# cnc.net
KiCad netlist of a schematic drawn in Altium Designer
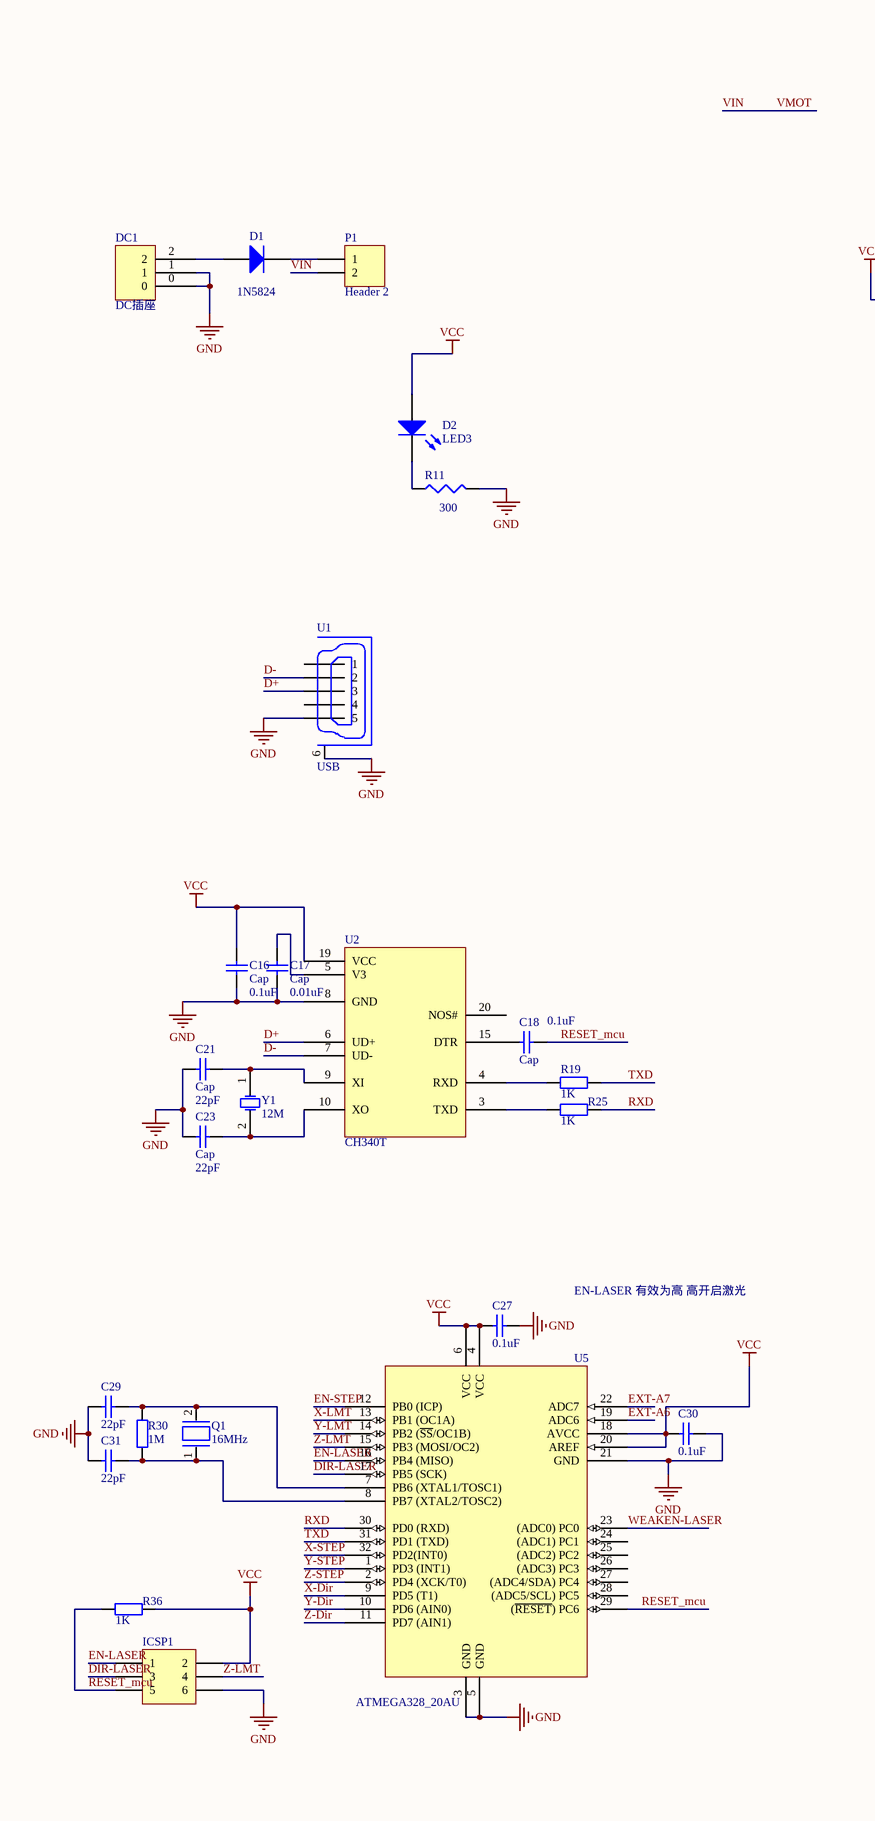
[diagram p0: cnc.SchDoc, left]
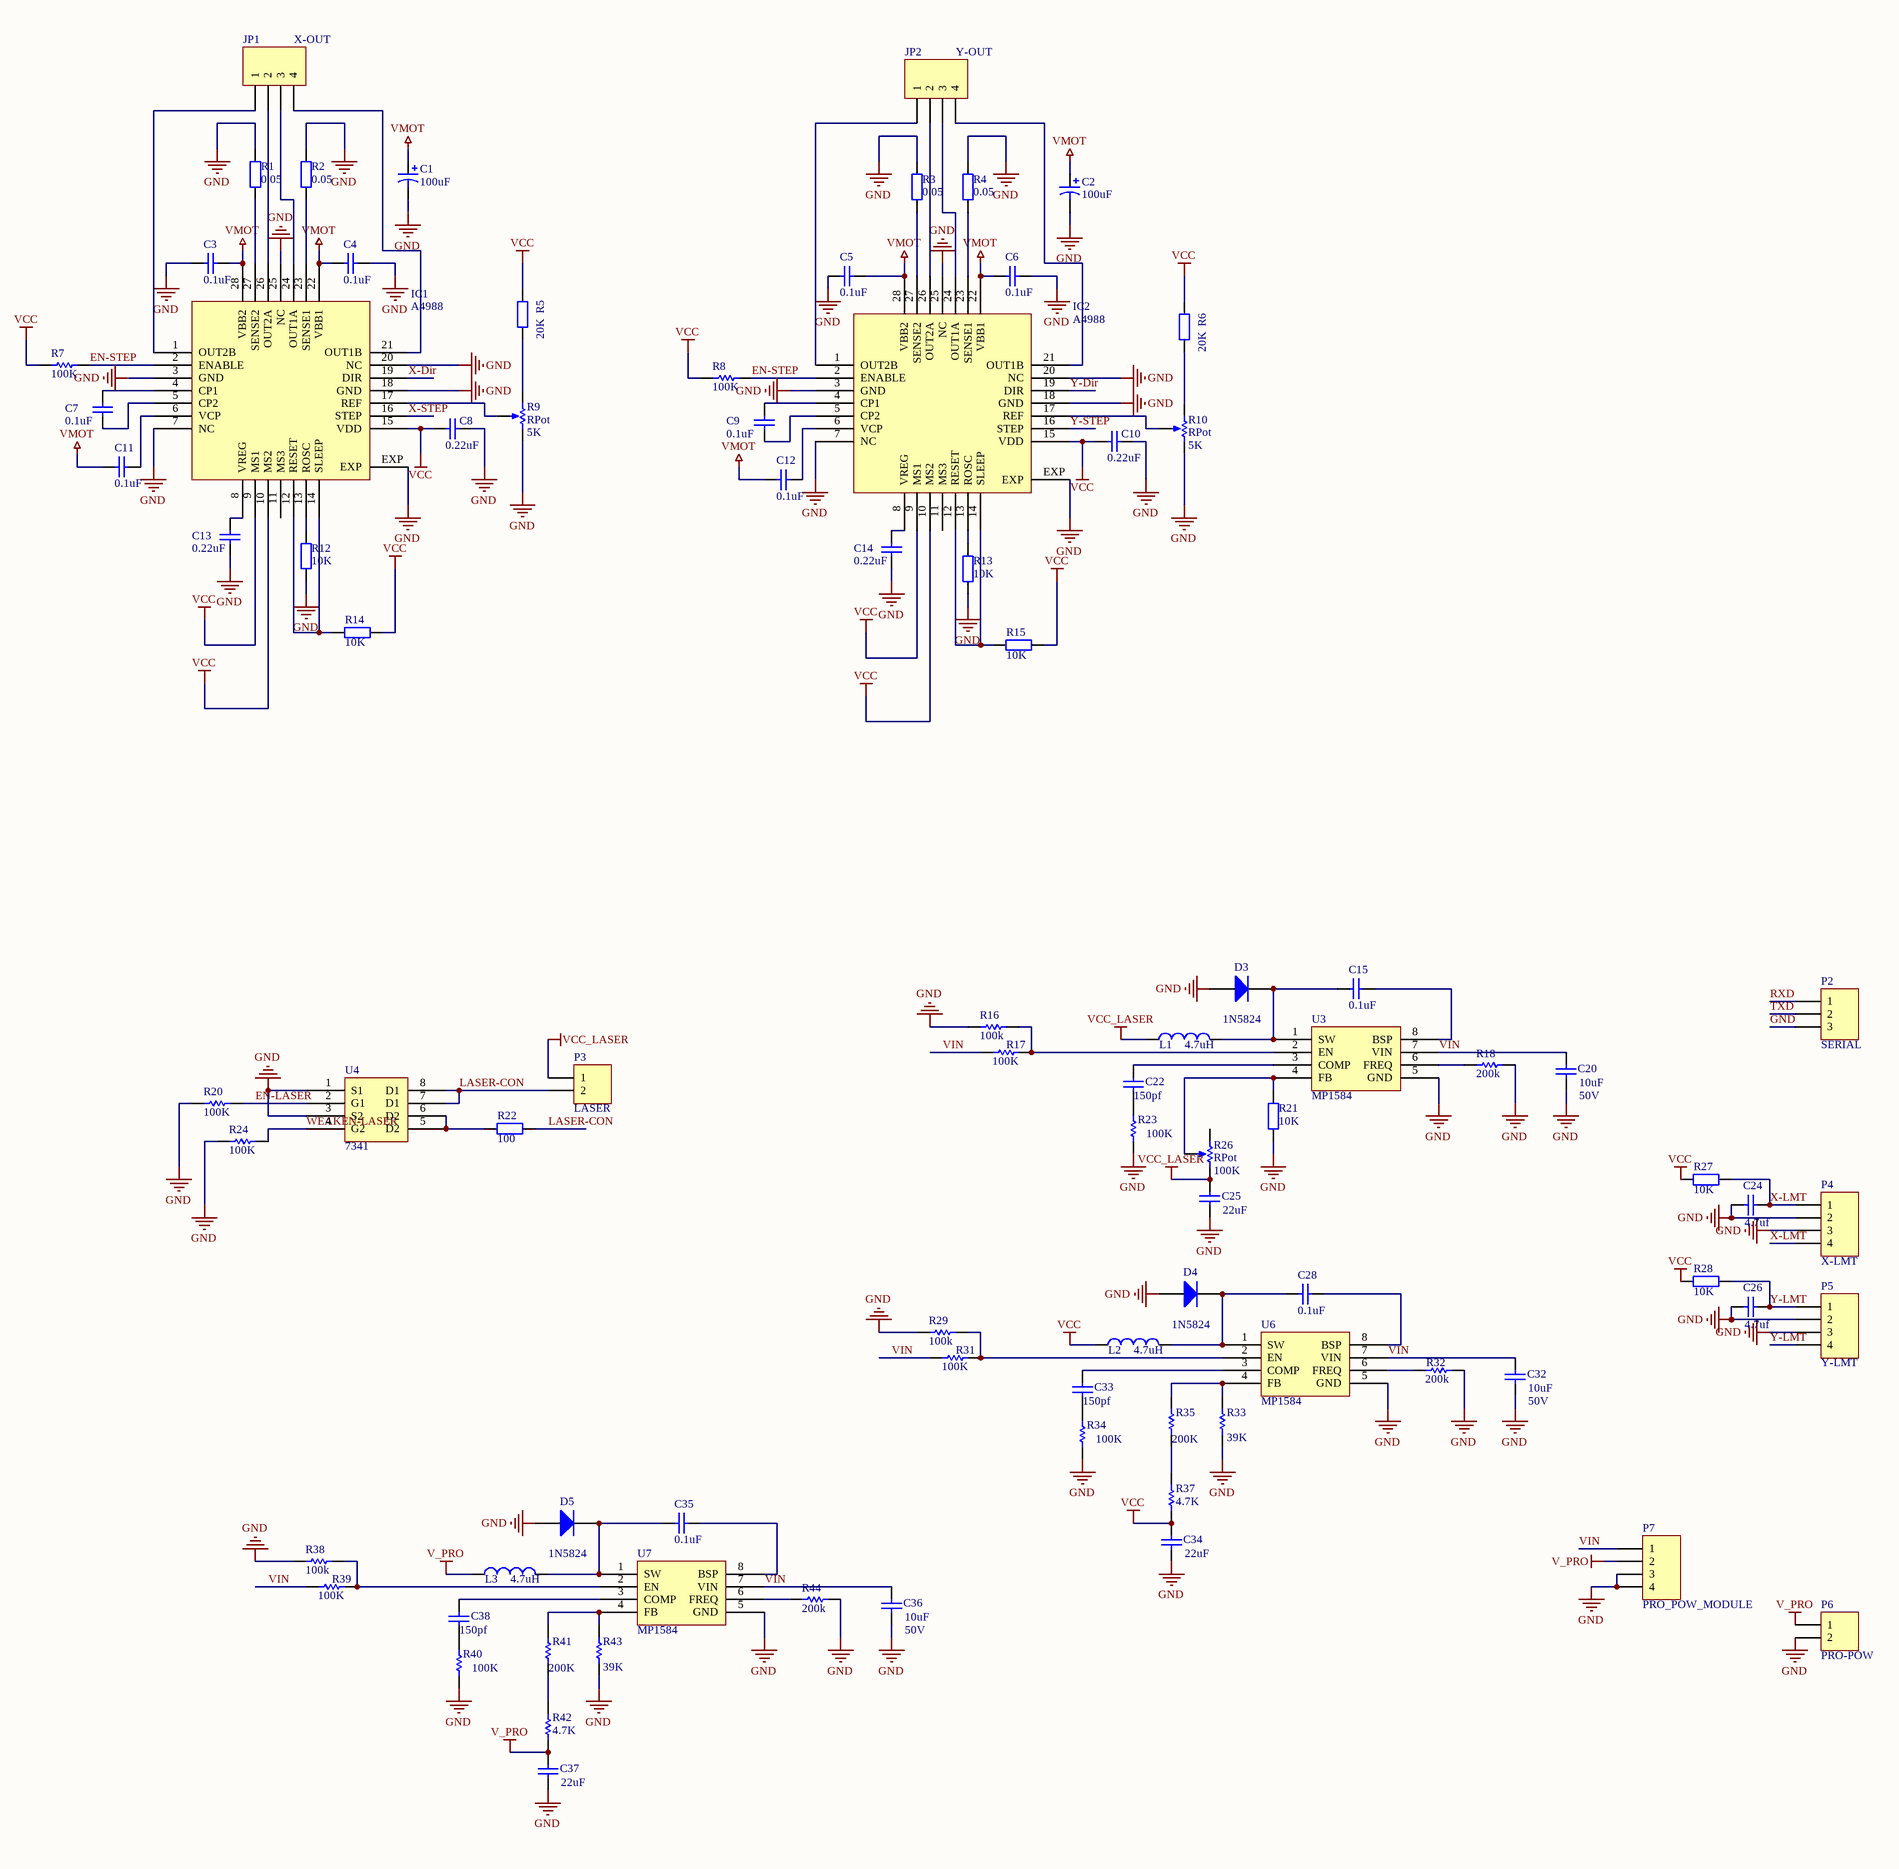
[diagram p1: cnc.SchDoc, right]

(export (version "E")
  (design (tool "Eeschema 10.0.6"))
  (components
    (comp (ref "C1")
      (value "100uF")
      (footprint "CD6032")
      (description "Polarized Capacitor (Radial)")
      (fields (field (name "Comment") "Cap Pol1") (field (name "PUBLISHER") "Altium Limited"))
      (libsource (lib "Miscellaneous Devices") (part "Cap Pol1"))
    )
    (comp (ref "C2")
      (value "100uF")
      (footprint "CD6032")
      (description "Polarized Capacitor (Radial)")
      (fields (field (name "Comment") "Cap Pol1") (field (name "PUBLISHER") "Altium Limited"))
      (libsource (lib "Miscellaneous Devices") (part "Cap Pol1"))
    )
    (comp (ref "C3")
      (value "0.1uF")
      (footprint "C0603")
      (description "Capacitor")
      (fields (field (name "Comment") "Cap") (field (name "PUBLISHER") "Altium Limited"))
      (libsource (lib "Miscellaneous Devices") (part "Cap"))
    )
    (comp (ref "C4")
      (value "0.1uF")
      (footprint "C0603")
      (description "Capacitor")
      (fields (field (name "Comment") "Cap") (field (name "PUBLISHER") "Altium Limited"))
      (libsource (lib "Miscellaneous Devices") (part "Cap"))
    )
    (comp (ref "C5")
      (value "0.1uF")
      (footprint "C0603")
      (description "Capacitor")
      (fields (field (name "Comment") "Cap") (field (name "PUBLISHER") "Altium Limited"))
      (libsource (lib "Miscellaneous Devices") (part "Cap"))
    )
    (comp (ref "C6")
      (value "0.1uF")
      (footprint "C0603")
      (description "Capacitor")
      (fields (field (name "Comment") "Cap") (field (name "PUBLISHER") "Altium Limited"))
      (libsource (lib "Miscellaneous Devices") (part "Cap"))
    )
    (comp (ref "C7")
      (value "0.1uF")
      (footprint "C0603")
      (description "Capacitor")
      (fields (field (name "Comment") "Cap") (field (name "PUBLISHER") "Altium Limited"))
      (libsource (lib "Miscellaneous Devices") (part "Cap"))
    )
    (comp (ref "C8")
      (value "0.22uF")
      (footprint "C0603")
      (description "Capacitor")
      (fields (field (name "Comment") "Cap") (field (name "PUBLISHER") "Altium Limited"))
      (libsource (lib "Miscellaneous Devices") (part "Cap"))
    )
    (comp (ref "C9")
      (value "0.1uF")
      (footprint "C0603")
      (description "Capacitor")
      (fields (field (name "Comment") "Cap") (field (name "PUBLISHER") "Altium Limited"))
      (libsource (lib "Miscellaneous Devices") (part "Cap"))
    )
    (comp (ref "C10")
      (value "0.22uF")
      (footprint "C0603")
      (description "Capacitor")
      (fields (field (name "Comment") "Cap") (field (name "PUBLISHER") "Altium Limited"))
      (libsource (lib "Miscellaneous Devices") (part "Cap"))
    )
    (comp (ref "C11")
      (value "0.1uF")
      (footprint "C0603")
      (description "Capacitor")
      (fields (field (name "Comment") "Cap") (field (name "PUBLISHER") "Altium Limited"))
      (libsource (lib "Miscellaneous Devices") (part "Cap"))
    )
    (comp (ref "C12")
      (value "0.1uF")
      (footprint "C0603")
      (description "Capacitor")
      (fields (field (name "Comment") "Cap") (field (name "PUBLISHER") "Altium Limited"))
      (libsource (lib "Miscellaneous Devices") (part "Cap"))
    )
    (comp (ref "C13")
      (value "0.22uF")
      (footprint "C0603")
      (description "Capacitor")
      (fields (field (name "Comment") "Cap") (field (name "PUBLISHER") "Altium Limited"))
      (libsource (lib "Miscellaneous Devices") (part "Cap"))
    )
    (comp (ref "C14")
      (value "0.22uF")
      (footprint "C0603")
      (description "Capacitor")
      (fields (field (name "Comment") "Cap") (field (name "PUBLISHER") "Altium Limited"))
      (libsource (lib "Miscellaneous Devices") (part "Cap"))
    )
    (comp (ref "C15")
      (value "0.1uF")
      (footprint "C0603")
      (description "Capacitor")
      (fields (field (name "Comment") "Cap") (field (name "PUBLISHER") "Altium Limited"))
      (libsource (lib "Miscellaneous Devices") (part "Cap"))
    )
    (comp (ref "C16")
      (value "Cap")
      (footprint "C0603")
      (description "Capacitor")
      (fields (field (name "ALTIUM_VALUE") "0.1uF") (field (name "PUBLISHER") "Altium Limited"))
      (libsource (lib "Miscellaneous Devices") (part "Cap"))
    )
    (comp (ref "C17")
      (value "Cap")
      (footprint "C0603")
      (description "Capacitor")
      (fields (field (name "ALTIUM_VALUE") "0.01uF") (field (name "PUBLISHER") "Altium Limited"))
      (libsource (lib "Miscellaneous Devices") (part "Cap"))
    )
    (comp (ref "C18")
      (value "Cap")
      (footprint "C0603")
      (description "Capacitor")
      (fields (field (name "ALTIUM_VALUE") "0.1uF") (field (name "PUBLISHER") "Altium Limited"))
      (libsource (lib "Miscellaneous Devices") (part "Cap"))
    )
    (comp (ref "C20")
      (value "50V")
      (footprint "C0603")
      (description "Capacitor")
      (fields (field (name "ALTIUM_VALUE") "10uF") (field (name "PUBLISHER") "Altium Limited"))
      (libsource (lib "Miscellaneous Devices") (part "Cap"))
    )
    (comp (ref "C21")
      (value "Cap")
      (footprint "C0603")
      (description "Capacitor")
      (fields (field (name "ALTIUM_VALUE") "22pF") (field (name "PUBLISHER") "Altium Limited"))
      (libsource (lib "Miscellaneous Devices") (part "Cap"))
    )
    (comp (ref "C22")
      (value "150pf")
      (footprint "C0603")
      (description "Capacitor")
      (fields (field (name "Comment") "Cap") (field (name "PUBLISHER") "Altium Limited"))
      (libsource (lib "Miscellaneous Devices") (part "Cap"))
    )
    (comp (ref "C23")
      (value "Cap")
      (footprint "C0603")
      (description "Capacitor")
      (fields (field (name "ALTIUM_VALUE") "22pF") (field (name "PUBLISHER") "Altium Limited"))
      (libsource (lib "Miscellaneous Devices") (part "Cap"))
    )
    (comp (ref "C24")
      (value "4.7uf")
      (footprint "C0603")
      (description "Capacitor")
      (fields (field (name "Comment") "Cap") (field (name "PUBLISHER") "Altium Limited"))
      (libsource (lib "Miscellaneous Devices") (part "Cap"))
    )
    (comp (ref "C25")
      (value "22uF")
      (footprint "C0603")
      (description "Capacitor")
      (fields (field (name "Comment") "Cap") (field (name "PUBLISHER") "Altium Limited"))
      (libsource (lib "Miscellaneous Devices") (part "Cap"))
    )
    (comp (ref "C26")
      (value "4.7uf")
      (footprint "C0603")
      (description "Capacitor")
      (fields (field (name "Comment") "Cap") (field (name "PUBLISHER") "Altium Limited"))
      (libsource (lib "Miscellaneous Devices") (part "Cap"))
    )
    (comp (ref "C27")
      (value "0.1uF")
      (footprint "C0603")
      (description "Capacitor")
      (fields (field (name "Comment") "Cap") (field (name "PUBLISHER") "Altium Limited"))
      (libsource (lib "Miscellaneous Devices") (part "Cap"))
    )
    (comp (ref "C28")
      (value "0.1uF")
      (footprint "C0603")
      (description "Capacitor")
      (fields (field (name "Comment") "Cap") (field (name "PUBLISHER") "Altium Limited"))
      (libsource (lib "Miscellaneous Devices") (part "Cap"))
    )
    (comp (ref "C29")
      (value "22pF")
      (footprint "C0603")
      (description "Capacitor")
      (fields (field (name "Comment") "Cap") (field (name "PUBLISHER") "Altium Limited"))
      (libsource (lib "Miscellaneous Devices") (part "Cap"))
    )
    (comp (ref "C30")
      (value "0.1uF")
      (footprint "C0603")
      (description "Capacitor")
      (fields (field (name "Comment") "Cap") (field (name "PUBLISHER") "Altium Limited"))
      (libsource (lib "Miscellaneous Devices") (part "Cap"))
    )
    (comp (ref "C31")
      (value "22pF")
      (footprint "C0603")
      (description "Capacitor")
      (fields (field (name "Comment") "Cap") (field (name "PUBLISHER") "Altium Limited"))
      (libsource (lib "Miscellaneous Devices") (part "Cap"))
    )
    (comp (ref "C32")
      (value "50V")
      (footprint "C0603")
      (description "Capacitor")
      (fields (field (name "ALTIUM_VALUE") "10uF") (field (name "PUBLISHER") "Altium Limited"))
      (libsource (lib "Miscellaneous Devices") (part "Cap"))
    )
    (comp (ref "C33")
      (value "150pf")
      (footprint "C0603")
      (description "Capacitor")
      (fields (field (name "Comment") "Cap") (field (name "PUBLISHER") "Altium Limited"))
      (libsource (lib "Miscellaneous Devices") (part "Cap"))
    )
    (comp (ref "C34")
      (value "22uF")
      (footprint "C0603")
      (description "Capacitor")
      (fields (field (name "Comment") "Cap") (field (name "PUBLISHER") "Altium Limited"))
      (libsource (lib "Miscellaneous Devices") (part "Cap"))
    )
    (comp (ref "C35")
      (value "0.1uF")
      (footprint "C0603")
      (description "Capacitor")
      (fields (field (name "Comment") "Cap") (field (name "PUBLISHER") "Altium Limited"))
      (libsource (lib "Miscellaneous Devices") (part "Cap"))
    )
    (comp (ref "C36")
      (value "50V")
      (footprint "C0603")
      (description "Capacitor")
      (fields (field (name "ALTIUM_VALUE") "10uF") (field (name "PUBLISHER") "Altium Limited"))
      (libsource (lib "Miscellaneous Devices") (part "Cap"))
    )
    (comp (ref "C37")
      (value "22uF")
      (footprint "C0603")
      (description "Capacitor")
      (fields (field (name "Comment") "Cap") (field (name "PUBLISHER") "Altium Limited"))
      (libsource (lib "Miscellaneous Devices") (part "Cap"))
    )
    (comp (ref "C38")
      (value "150pf")
      (footprint "C0603")
      (description "Capacitor")
      (fields (field (name "Comment") "Cap") (field (name "PUBLISHER") "Altium Limited"))
      (libsource (lib "Miscellaneous Devices") (part "Cap"))
    )
    (comp (ref "D1")
      (value "1N5824")
      (footprint "SS34")
      (description "1 Amp General Purpose Rectifier")
      (fields (field (name "PUBLISHER") "Altium Limited"))
      (libsource (lib "Miscellaneous Devices") (part "Diode 1N4007"))
    )
    (comp (ref "D2")
      (value "LED3")
      (footprint "LED")
      (description "Typical BLUE SiC LED")
      (fields (field (name "PUBLISHER") "Altium Limited"))
      (libsource (lib "Miscellaneous Devices") (part "LED3"))
    )
    (comp (ref "D3")
      (value "1N5824")
      (footprint "SS34")
      (description "1 Amp General Purpose Rectifier")
      (fields (field (name "PUBLISHER") "Altium Limited"))
      (libsource (lib "Miscellaneous Devices") (part "Diode 1N4007"))
    )
    (comp (ref "D4")
      (value "1N5824")
      (footprint "SS34")
      (description "1 Amp General Purpose Rectifier")
      (fields (field (name "PUBLISHER") "Altium Limited"))
      (libsource (lib "Miscellaneous Devices") (part "Diode 1N4007"))
    )
    (comp (ref "D5")
      (value "1N5824")
      (footprint "SS34")
      (description "1 Amp General Purpose Rectifier")
      (fields (field (name "PUBLISHER") "Altium Limited"))
      (libsource (lib "Miscellaneous Devices") (part "Diode 1N4007"))
    )
    (comp (ref "DC1") (value "DC插座") (footprint "DC座") (libsource (lib "dc") (part "DC插座")))
    (comp (ref "IC1") (value "A4988") (footprint "QFN28ET") (libsource (lib "Schlib1") (part "A4988")))
    (comp (ref "IC2") (value "A4988") (footprint "QFN28ET") (libsource (lib "Schlib1") (part "A4988")))
    (comp (ref "ICSP1")
      (value "Header 3X2")
      (footprint "HDR2X3")
      (description "Header, 3-Pin, Dual row")
      (fields (field (name "PUBLISHER") "Altium Limited"))
      (libsource (lib "Miscellaneous Connectors") (part "Header 3X2"))
    )
    (comp (ref "JP1")
      (value "X-OUT")
      (footprint "XH-2.54-4")
      (description "Header, 4-Pin")
      (fields (field (name "PUBLISHER") "Altium Limited"))
      (libsource (lib "") (part "Header 4_1"))
    )
    (comp (ref "JP2")
      (value "Y-OUT")
      (footprint "XH-2.54-4")
      (description "Header, 4-Pin")
      (fields (field (name "PUBLISHER") "Altium Limited"))
      (libsource (lib "") (part "Header 4_1"))
    )
    (comp (ref "L1")
      (value "4.7uH")
      (footprint "L_1584")
      (description "Inductor")
      (fields (field (name "PUBLISHER") "Altium Limited"))
      (libsource (lib "Miscellaneous Devices") (part "Inductor"))
    )
    (comp (ref "L2")
      (value "4.7uH")
      (footprint "L_1584")
      (description "Inductor")
      (fields (field (name "PUBLISHER") "Altium Limited"))
      (libsource (lib "Miscellaneous Devices") (part "Inductor"))
    )
    (comp (ref "L3")
      (value "4.7uH")
      (footprint "L_1584")
      (description "Inductor")
      (fields (field (name "PUBLISHER") "Altium Limited"))
      (libsource (lib "Miscellaneous Devices") (part "Inductor"))
    )
    (comp (ref "P1")
      (value "Header 2")
      (footprint "XH-2.54-2")
      (description "Header, 2-Pin")
      (fields (field (name "PUBLISHER") "Altium Limited"))
      (libsource (lib "Miscellaneous Connectors") (part "Header 2"))
    )
    (comp (ref "P2")
      (value "SERIAL")
      (footprint "HDR1X3")
      (description "Header, 3-Pin")
      (fields (field (name "PUBLISHER") "Altium Limited"))
      (libsource (lib "Miscellaneous Connectors") (part "Header 3"))
    )
    (comp (ref "P3")
      (value "LASER")
      (footprint "XH-2.54-2")
      (description "Header, 2-Pin")
      (fields (field (name "PUBLISHER") "Altium Limited"))
      (libsource (lib "Miscellaneous Connectors") (part "Header 2"))
    )
    (comp (ref "P4")
      (value "X-LMT")
      (footprint "XH-2.54-4")
      (description "Header, 4-Pin")
      (fields (field (name "PUBLISHER") "Altium Limited"))
      (libsource (lib "Miscellaneous Connectors") (part "Header 4"))
    )
    (comp (ref "P5")
      (value "Y-LMT")
      (footprint "XH-2.54-4")
      (description "Header, 4-Pin")
      (fields (field (name "PUBLISHER") "Altium Limited"))
      (libsource (lib "Miscellaneous Connectors") (part "Header 4"))
    )
    (comp (ref "P6")
      (value "PRO-POW")
      (footprint "XH-2.54-2")
      (description "Header, 2-Pin")
      (fields (field (name "PUBLISHER") "Altium Limited"))
      (libsource (lib "Miscellaneous Connectors") (part "Header 2"))
    )
    (comp (ref "P7")
      (value "PRO_POW_MODULE")
      (footprint "mp1584module")
      (description "Header, 4-Pin")
      (fields (field (name "PUBLISHER") "Altium Limited"))
      (libsource (lib "Miscellaneous Connectors") (part "Header 4"))
    )
    (comp (ref "Q1")
      (value "16MHz")
      (footprint "QS")
      (libsource (lib "Arduino_MEGA2560_ref_1") (part "XTAL/S"))
    )
    (comp (ref "R1")
      (value "0.05")
      (footprint "1206")
      (description "Resistor")
      (fields (field (name "Comment") "Res2") (field (name "PUBLISHER") "Altium Limited"))
      (libsource (lib "Miscellaneous Devices") (part "Res2"))
    )
    (comp (ref "R2")
      (value "0.05")
      (footprint "1206")
      (description "Resistor")
      (fields (field (name "Comment") "Res2") (field (name "PUBLISHER") "Altium Limited"))
      (libsource (lib "Miscellaneous Devices") (part "Res2"))
    )
    (comp (ref "R3")
      (value "0.05")
      (footprint "1206")
      (description "Resistor")
      (fields (field (name "Comment") "Res2") (field (name "PUBLISHER") "Altium Limited"))
      (libsource (lib "Miscellaneous Devices") (part "Res2"))
    )
    (comp (ref "R4")
      (value "0.05")
      (footprint "1206")
      (description "Resistor")
      (fields (field (name "Comment") "Res2") (field (name "PUBLISHER") "Altium Limited"))
      (libsource (lib "Miscellaneous Devices") (part "Res2"))
    )
    (comp (ref "R5")
      (value "20K")
      (footprint "R0603")
      (description "Resistor")
      (fields (field (name "Comment") "Res2") (field (name "PUBLISHER") "Altium Limited"))
      (libsource (lib "Miscellaneous Devices") (part "Res2"))
    )
    (comp (ref "R6")
      (value "20K")
      (footprint "R0603")
      (description "Resistor")
      (fields (field (name "Comment") "Res2") (field (name "PUBLISHER") "Altium Limited"))
      (libsource (lib "Miscellaneous Devices") (part "Res2"))
    )
    (comp (ref "R7")
      (value "100K")
      (footprint "R0603")
      (description "Resistor")
      (fields (field (name "Comment") "Res1") (field (name "PUBLISHER") "Altium Limited"))
      (libsource (lib "Miscellaneous Devices") (part "Res1"))
    )
    (comp (ref "R8")
      (value "100K")
      (footprint "R0603")
      (description "Resistor")
      (fields (field (name "Comment") "Res1") (field (name "PUBLISHER") "Altium Limited"))
      (libsource (lib "Miscellaneous Devices") (part "Res1"))
    )
    (comp (ref "R9")
      (value "RPot")
      (footprint "电位器")
      (description "Potentiometer")
      (fields (field (name "ALTIUM_VALUE") "5K") (field (name "PUBLISHER") "Altium Limited"))
      (libsource (lib "Miscellaneous Devices") (part "RPot"))
    )
    (comp (ref "R10")
      (value "RPot")
      (footprint "电位器")
      (description "Potentiometer")
      (fields (field (name "ALTIUM_VALUE") "5K") (field (name "PUBLISHER") "Altium Limited"))
      (libsource (lib "Miscellaneous Devices") (part "RPot"))
    )
    (comp (ref "R11")
      (value "300")
      (footprint "R0603")
      (description "Resistor")
      (fields (field (name "Comment") "Res3") (field (name "PUBLISHER") "Altium Limited"))
      (libsource (lib "Miscellaneous Devices") (part "Res3"))
    )
    (comp (ref "R12")
      (value "10K")
      (footprint "R0603")
      (description "Resistor")
      (fields (field (name "Comment") "Res2") (field (name "PUBLISHER") "Altium Limited"))
      (libsource (lib "Miscellaneous Devices") (part "Res2"))
    )
    (comp (ref "R13")
      (value "10K")
      (footprint "R0603")
      (description "Resistor")
      (fields (field (name "Comment") "Res2") (field (name "PUBLISHER") "Altium Limited"))
      (libsource (lib "Miscellaneous Devices") (part "Res2"))
    )
    (comp (ref "R14")
      (value "10K")
      (footprint "R0603")
      (description "Resistor")
      (fields (field (name "Comment") "Res2") (field (name "PUBLISHER") "Altium Limited"))
      (libsource (lib "") (part "Res2_2"))
    )
    (comp (ref "R15")
      (value "10K")
      (footprint "R0603")
      (description "Resistor")
      (fields (field (name "Comment") "Res2") (field (name "PUBLISHER") "Altium Limited"))
      (libsource (lib "") (part "Res2_2"))
    )
    (comp (ref "R16")
      (value "100k")
      (footprint "R0603")
      (description "Resistor")
      (fields (field (name "Comment") "Res1") (field (name "PUBLISHER") "Altium Limited"))
      (libsource (lib "Miscellaneous Devices") (part "Res1"))
    )
    (comp (ref "R17")
      (value "100K")
      (footprint "R0603")
      (description "Resistor")
      (fields (field (name "Comment") "Res1") (field (name "PUBLISHER") "Altium Limited"))
      (libsource (lib "Miscellaneous Devices") (part "Res1"))
    )
    (comp (ref "R18")
      (value "200k")
      (footprint "R0603")
      (description "Resistor")
      (fields (field (name "Comment") "Res1") (field (name "PUBLISHER") "Altium Limited"))
      (libsource (lib "Miscellaneous Devices") (part "Res1"))
    )
    (comp (ref "R19")
      (value "1K")
      (footprint "R0603")
      (description "Resistor")
      (fields (field (name "Comment") "Res2") (field (name "PUBLISHER") "Altium Limited"))
      (libsource (lib "") (part "Res2_1"))
    )
    (comp (ref "R20")
      (value "100K")
      (footprint "R0603")
      (description "Resistor")
      (fields (field (name "Comment") "Res1") (field (name "PUBLISHER") "Altium Limited"))
      (libsource (lib "Miscellaneous Devices") (part "Res1"))
    )
    (comp (ref "R21")
      (value "10K")
      (footprint "R0603")
      (description "Resistor")
      (fields (field (name "Comment") "Res2") (field (name "PUBLISHER") "Altium Limited"))
      (libsource (lib "Miscellaneous Devices") (part "Res2"))
    )
    (comp (ref "R22")
      (value "100")
      (footprint "R0603")
      (description "Resistor")
      (fields (field (name "Comment") "Res2") (field (name "PUBLISHER") "Altium Limited"))
      (libsource (lib "") (part "Res2_1"))
    )
    (comp (ref "R23")
      (value "100K")
      (footprint "R0603")
      (description "Resistor")
      (fields (field (name "Comment") "Res1") (field (name "PUBLISHER") "Altium Limited"))
      (libsource (lib "Miscellaneous Devices") (part "Res1"))
    )
    (comp (ref "R24")
      (value "100K")
      (footprint "R0603")
      (description "Resistor")
      (fields (field (name "Comment") "Res1") (field (name "PUBLISHER") "Altium Limited"))
      (libsource (lib "Miscellaneous Devices") (part "Res1"))
    )
    (comp (ref "R25")
      (value "1K")
      (footprint "R0603")
      (description "Resistor")
      (fields (field (name "Comment") "Res2") (field (name "PUBLISHER") "Altium Limited"))
      (libsource (lib "") (part "Res2_2"))
    )
    (comp (ref "R26")
      (value "RPot")
      (footprint "电位器")
      (description "Potentiometer")
      (fields (field (name "ALTIUM_VALUE") "100K") (field (name "PUBLISHER") "Altium Limited"))
      (libsource (lib "Miscellaneous Devices") (part "RPot"))
    )
    (comp (ref "R27")
      (value "10K")
      (footprint "R0603")
      (description "Resistor")
      (fields (field (name "Comment") "Res2") (field (name "PUBLISHER") "Altium Limited"))
      (libsource (lib "") (part "Res2_1"))
    )
    (comp (ref "R28")
      (value "10K")
      (footprint "R0603")
      (description "Resistor")
      (fields (field (name "Comment") "Res2") (field (name "PUBLISHER") "Altium Limited"))
      (libsource (lib "") (part "Res2_1"))
    )
    (comp (ref "R29")
      (value "100k")
      (footprint "R0603")
      (description "Resistor")
      (fields (field (name "Comment") "Res1") (field (name "PUBLISHER") "Altium Limited"))
      (libsource (lib "Miscellaneous Devices") (part "Res1"))
    )
    (comp (ref "R30")
      (value "1M")
      (footprint "R0603")
      (description "Resistor")
      (fields (field (name "Comment") "Res2") (field (name "PUBLISHER") "Altium Limited"))
      (libsource (lib "") (part "Res2_3"))
    )
    (comp (ref "R31")
      (value "100K")
      (footprint "R0603")
      (description "Resistor")
      (fields (field (name "Comment") "Res1") (field (name "PUBLISHER") "Altium Limited"))
      (libsource (lib "Miscellaneous Devices") (part "Res1"))
    )
    (comp (ref "R32")
      (value "200k")
      (footprint "R0603")
      (description "Resistor")
      (fields (field (name "Comment") "Res1") (field (name "PUBLISHER") "Altium Limited"))
      (libsource (lib "Miscellaneous Devices") (part "Res1"))
    )
    (comp (ref "R33")
      (value "39K")
      (footprint "R0603")
      (description "Resistor")
      (fields (field (name "Comment") "Res1") (field (name "PUBLISHER") "Altium Limited"))
      (libsource (lib "Miscellaneous Devices") (part "Res1"))
    )
    (comp (ref "R34")
      (value "100K")
      (footprint "R0603")
      (description "Resistor")
      (fields (field (name "Comment") "Res1") (field (name "PUBLISHER") "Altium Limited"))
      (libsource (lib "Miscellaneous Devices") (part "Res1"))
    )
    (comp (ref "R35")
      (value "200K")
      (footprint "R0603")
      (description "Resistor")
      (fields (field (name "Comment") "Res1") (field (name "PUBLISHER") "Altium Limited"))
      (libsource (lib "Miscellaneous Devices") (part "Res1"))
    )
    (comp (ref "R36")
      (value "1K")
      (footprint "R0603")
      (description "Resistor")
      (fields (field (name "Comment") "Res2") (field (name "PUBLISHER") "Altium Limited"))
      (libsource (lib "") (part "Res2_2"))
    )
    (comp (ref "R37")
      (value "4.7K")
      (footprint "R0603")
      (description "Resistor")
      (fields (field (name "Comment") "Res1") (field (name "PUBLISHER") "Altium Limited"))
      (libsource (lib "Miscellaneous Devices") (part "Res1"))
    )
    (comp (ref "R38")
      (value "100k")
      (footprint "R0603")
      (description "Resistor")
      (fields (field (name "Comment") "Res1") (field (name "PUBLISHER") "Altium Limited"))
      (libsource (lib "Miscellaneous Devices") (part "Res1"))
    )
    (comp (ref "R39")
      (value "100K")
      (footprint "R0603")
      (description "Resistor")
      (fields (field (name "Comment") "Res1") (field (name "PUBLISHER") "Altium Limited"))
      (libsource (lib "Miscellaneous Devices") (part "Res1"))
    )
    (comp (ref "R40")
      (value "100K")
      (footprint "R0603")
      (description "Resistor")
      (fields (field (name "Comment") "Res1") (field (name "PUBLISHER") "Altium Limited"))
      (libsource (lib "Miscellaneous Devices") (part "Res1"))
    )
    (comp (ref "R41")
      (value "200K")
      (footprint "R0603")
      (description "Resistor")
      (fields (field (name "Comment") "Res1") (field (name "PUBLISHER") "Altium Limited"))
      (libsource (lib "Miscellaneous Devices") (part "Res1"))
    )
    (comp (ref "R42")
      (value "4.7K")
      (footprint "R0603")
      (description "Resistor")
      (fields (field (name "Comment") "Res1") (field (name "PUBLISHER") "Altium Limited"))
      (libsource (lib "Miscellaneous Devices") (part "Res1"))
    )
    (comp (ref "R43")
      (value "39K")
      (footprint "R0603")
      (description "Resistor")
      (fields (field (name "Comment") "Res1") (field (name "PUBLISHER") "Altium Limited"))
      (libsource (lib "Miscellaneous Devices") (part "Res1"))
    )
    (comp (ref "R44")
      (value "200k")
      (footprint "R0603")
      (description "Resistor")
      (fields (field (name "Comment") "Res1") (field (name "PUBLISHER") "Altium Limited"))
      (libsource (lib "Miscellaneous Devices") (part "Res1"))
    )
    (comp (ref "U1")
      (value "USB")
      (footprint "MICRO-USB")
      (libsource (lib "cnc") (part "MOLEX_MICRO_USB_AB_BOTTOM_MOUNT"))
    )
    (comp (ref "U2") (value "CH340T") (footprint "SSOP-20") (libsource (lib "seeker1_0_cpu") (part "CH340T")))
    (comp (ref "U3")
      (value "MP1584")
      (footprint "SOIC127P720X170-8N")
      (libsource (lib "seeker1_0") (part "MP1584"))
    )
    (comp (ref "U4")
      (value "7341")
      (footprint "SOIC127P720X170-8N")
      (libsource (lib "7341") (part "Component_1"))
    )
    (comp (ref "U5")
      (value "ATMEGA328_20AU")
      (footprint "TQFP32")
      (description "Atmel Microcontroller - Library created by carel..  <www.mpfreezone.com>")
      (libsource (lib "AVR") (part "ATMEGA8_TQFP32"))
    )
    (comp (ref "U6")
      (value "MP1584")
      (footprint "SOIC127P720X170-8N")
      (libsource (lib "seeker1_0") (part "MP1584"))
    )
    (comp (ref "U7")
      (value "MP1584")
      (footprint "SOIC127P720X170-8N")
      (libsource (lib "seeker1_0") (part "MP1584"))
    )
    (comp (ref "Y1")
      (value "12M")
      (footprint "QS")
      (description "Crystal Oscillator")
      (fields (field (name "PUBLISHER") "Altium Limited"))
      (libsource (lib "Miscellaneous Devices") (part "XTAL"))
    )
  )
  (nets
    (net (code "1") (name "/D+") (class "Default")
      (node (ref "U1") (pin "3") (pinfunction "3_3") (pintype "passive"))
      (node (ref "U2") (pin "6") (pinfunction "UD+_6") (pintype "passive"))
    )
    (net (code "2") (name "/D-") (class "Default")
      (node (ref "U1") (pin "2") (pinfunction "2_2") (pintype "passive"))
      (node (ref "U2") (pin "7") (pinfunction "UD-_7") (pintype "passive"))
    )
    (net (code "3") (name "/DIR-LASER") (class "Default")
      (node (ref "ICSP1") (pin "3") (pinfunction "3_3") (pintype "passive"))
      (node (ref "U5") (pin "17") (pinfunction "PB5_(SCK)_17") (pintype "bidirectional"))
    )
    (net (code "4") (name "/EN-LASER") (class "Default")
      (node (ref "ICSP1") (pin "1") (pinfunction "1_1") (pintype "passive"))
      (node (ref "R20") (pin "1") (pinfunction "1_1") (pintype "passive"))
      (node (ref "U4") (pin "2") (pinfunction "G1_2") (pintype "passive"))
      (node (ref "U5") (pin "16") (pinfunction "PB4_(MISO)_16") (pintype "bidirectional"))
    )
    (net (code "5") (name "/EN-STEP") (class "Default")
      (node (ref "IC1") (pin "2") (pinfunction "ENABLE_2") (pintype "passive"))
      (node (ref "IC2") (pin "2") (pinfunction "ENABLE_2") (pintype "passive"))
      (node (ref "R7") (pin "1") (pinfunction "1_1") (pintype "passive"))
      (node (ref "R8") (pin "1") (pinfunction "1_1") (pintype "passive"))
      (node (ref "U5") (pin "12") (pinfunction "PB0_(ICP)_12") (pintype "passive"))
    )
    (net (code "6") (name "/EXT-A6") (class "Default")
      (node (ref "U5") (pin "19") (pinfunction "ADC6_19") (pintype "input"))
    )
    (net (code "7") (name "/EXT-A7") (class "Default")
      (node (ref "U5") (pin "22") (pinfunction "ADC7_22") (pintype "input"))
    )
    (net (code "8") (name "/LASER-CON") (class "Default")
      (node (ref "P3") (pin "2") (pinfunction "2_2") (pintype "passive"))
      (node (ref "R22") (pin "1") (pinfunction "1_1") (pintype "passive"))
      (node (ref "U4") (pin "7") (pinfunction "D1_7") (pintype "passive"))
      (node (ref "U4") (pin "8") (pinfunction "D1_8") (pintype "passive"))
    )
    (net (code "9") (name "/RESET_mcu") (class "Default")
      (node (ref "C18") (pin "2") (pinfunction "2_2") (pintype "passive"))
      (node (ref "ICSP1") (pin "5") (pinfunction "5_5") (pintype "passive"))
      (node (ref "R36") (pin "1") (pinfunction "1_1") (pintype "passive"))
      (node (ref "U5") (pin "29") (pinfunction "(~{RESET})_PC6_29") (pintype "bidirectional"))
    )
    (net (code "10") (name "/RXD") (class "Default")
      (node (ref "P2") (pin "1") (pinfunction "1_1") (pintype "passive"))
      (node (ref "R25") (pin "2") (pinfunction "2_2") (pintype "passive"))
      (node (ref "U5") (pin "30") (pinfunction "PD0_(RXD)_30") (pintype "bidirectional"))
    )
    (net (code "11") (name "/TXD") (class "Default")
      (node (ref "P2") (pin "2") (pinfunction "2_2") (pintype "passive"))
      (node (ref "R19") (pin "1") (pinfunction "1_1") (pintype "passive"))
      (node (ref "U5") (pin "31") (pinfunction "PD1_(TXD)_31") (pintype "bidirectional"))
    )
    (net (code "12") (name "/WEAKEN-LASER") (class "Default")
      (node (ref "R24") (pin "1") (pinfunction "1_1") (pintype "passive"))
      (node (ref "U4") (pin "4") (pinfunction "G2_4") (pintype "passive"))
      (node (ref "U5") (pin "23") (pinfunction "(ADC0)_PC0_23") (pintype "bidirectional"))
    )
    (net (code "13") (name "/X-Dir") (class "Default")
      (node (ref "IC1") (pin "19") (pinfunction "DIR_19") (pintype "passive"))
      (node (ref "U5") (pin "9") (pinfunction "PD5_(T1)_9") (pintype "passive"))
    )
    (net (code "14") (name "/X-LMT") (class "Default")
      (node (ref "C24") (pin "1") (pinfunction "1_1") (pintype "passive"))
      (node (ref "P4") (pin "1") (pinfunction "1_1") (pintype "passive"))
      (node (ref "P4") (pin "4") (pinfunction "4_4") (pintype "passive"))
      (node (ref "R27") (pin "1") (pinfunction "1_1") (pintype "passive"))
      (node (ref "U5") (pin "13") (pinfunction "PB1_(OC1A)_13") (pintype "bidirectional"))
    )
    (net (code "15") (name "/X-STEP") (class "Default")
      (node (ref "IC1") (pin "16") (pinfunction "STEP_16") (pintype "passive"))
      (node (ref "U5") (pin "32") (pinfunction "PD2(INT0)_32") (pintype "bidirectional"))
    )
    (net (code "16") (name "/Y-Dir") (class "Default")
      (node (ref "IC2") (pin "19") (pinfunction "DIR_19") (pintype "passive"))
      (node (ref "U5") (pin "10") (pinfunction "PD6_(AIN0)_10") (pintype "passive"))
    )
    (net (code "17") (name "/Y-LMT") (class "Default")
      (node (ref "C26") (pin "1") (pinfunction "1_1") (pintype "passive"))
      (node (ref "P5") (pin "1") (pinfunction "1_1") (pintype "passive"))
      (node (ref "P5") (pin "4") (pinfunction "4_4") (pintype "passive"))
      (node (ref "R28") (pin "1") (pinfunction "1_1") (pintype "passive"))
      (node (ref "U5") (pin "14") (pinfunction "PB2_(~{SS}/OC1B)_14") (pintype "bidirectional"))
    )
    (net (code "18") (name "/Y-STEP") (class "Default")
      (node (ref "IC2") (pin "16") (pinfunction "STEP_16") (pintype "passive"))
      (node (ref "U5") (pin "1") (pinfunction "PD3_(INT1)_1") (pintype "bidirectional"))
    )
    (net (code "19") (name "/Z-Dir") (class "Default")
      (node (ref "U5") (pin "11") (pinfunction "PD7_(AIN1)_11") (pintype "passive"))
    )
    (net (code "20") (name "/Z-LMT") (class "Default")
      (node (ref "ICSP1") (pin "4") (pinfunction "4_4") (pintype "passive"))
      (node (ref "U5") (pin "15") (pinfunction "PB3_(MOSI/OC2)_15") (pintype "bidirectional"))
    )
    (net (code "21") (name "/Z-STEP") (class "Default")
      (node (ref "U5") (pin "2") (pinfunction "PD4_(XCK/T0)_2") (pintype "bidirectional"))
    )
    (net (code "22") (name "GND") (class "Default")
      (node (ref "C1") (pin "2") (pinfunction "2_2") (pintype "passive"))
      (node (ref "C10") (pin "2") (pinfunction "2_2") (pintype "passive"))
      (node (ref "C13") (pin "1") (pinfunction "1_1") (pintype "passive"))
      (node (ref "C14") (pin "1") (pinfunction "1_1") (pintype "passive"))
      (node (ref "C16") (pin "1") (pinfunction "1_1") (pintype "passive"))
      (node (ref "C17") (pin "1") (pinfunction "1_1") (pintype "passive"))
      (node (ref "C2") (pin "2") (pinfunction "2_2") (pintype "passive"))
      (node (ref "C20") (pin "2") (pinfunction "2_2") (pintype "passive"))
      (node (ref "C21") (pin "1") (pinfunction "1_1") (pintype "passive"))
      (node (ref "C23") (pin "1") (pinfunction "1_1") (pintype "passive"))
      (node (ref "C24") (pin "2") (pinfunction "2_2") (pintype "passive"))
      (node (ref "C25") (pin "2") (pinfunction "2_2") (pintype "passive"))
      (node (ref "C26") (pin "2") (pinfunction "2_2") (pintype "passive"))
      (node (ref "C27") (pin "1") (pinfunction "1_1") (pintype "passive"))
      (node (ref "C29") (pin "2") (pinfunction "2_2") (pintype "passive"))
      (node (ref "C3") (pin "1") (pinfunction "1_1") (pintype "passive"))
      (node (ref "C30") (pin "1") (pinfunction "1_1") (pintype "passive"))
      (node (ref "C31") (pin "2") (pinfunction "2_2") (pintype "passive"))
      (node (ref "C32") (pin "2") (pinfunction "2_2") (pintype "passive"))
      (node (ref "C34") (pin "2") (pinfunction "2_2") (pintype "passive"))
      (node (ref "C36") (pin "2") (pinfunction "2_2") (pintype "passive"))
      (node (ref "C37") (pin "2") (pinfunction "2_2") (pintype "passive"))
      (node (ref "C4") (pin "2") (pinfunction "2_2") (pintype "passive"))
      (node (ref "C5") (pin "1") (pinfunction "1_1") (pintype "passive"))
      (node (ref "C6") (pin "2") (pinfunction "2_2") (pintype "passive"))
      (node (ref "C8") (pin "2") (pinfunction "2_2") (pintype "passive"))
      (node (ref "D3") (pin "1") (pinfunction "A_1") (pintype "passive"))
      (node (ref "D4") (pin "1") (pinfunction "A_1") (pintype "passive"))
      (node (ref "D5") (pin "1") (pinfunction "A_1") (pintype "passive"))
      (node (ref "DC1") (pin "0") (pinfunction "0_0") (pintype "passive"))
      (node (ref "DC1") (pin "1") (pinfunction "1_1") (pintype "passive"))
      (node (ref "IC1") (pin "18") (pinfunction "GND_18") (pintype "passive"))
      (node (ref "IC1") (pin "20") (pinfunction "NC_20") (pintype "passive"))
      (node (ref "IC1") (pin "25") (pinfunction "NC_25") (pintype "passive"))
      (node (ref "IC1") (pin "3") (pinfunction "GND_3") (pintype "passive"))
      (node (ref "IC1") (pin "7") (pinfunction "NC_7") (pintype "passive"))
      (node (ref "IC1") (pin "EXP") (pinfunction "EXP_EXP") (pintype "passive"))
      (node (ref "IC2") (pin "18") (pinfunction "GND_18") (pintype "passive"))
      (node (ref "IC2") (pin "20") (pinfunction "NC_20") (pintype "passive"))
      (node (ref "IC2") (pin "25") (pinfunction "NC_25") (pintype "passive"))
      (node (ref "IC2") (pin "3") (pinfunction "GND_3") (pintype "passive"))
      (node (ref "IC2") (pin "7") (pinfunction "NC_7") (pintype "passive"))
      (node (ref "IC2") (pin "EXP") (pinfunction "EXP_EXP") (pintype "passive"))
      (node (ref "ICSP1") (pin "6") (pinfunction "6_6") (pintype "passive"))
      (node (ref "P2") (pin "3") (pinfunction "3_3") (pintype "passive"))
      (node (ref "P4") (pin "2") (pinfunction "2_2") (pintype "passive"))
      (node (ref "P4") (pin "3") (pinfunction "3_3") (pintype "passive"))
      (node (ref "P5") (pin "2") (pinfunction "2_2") (pintype "passive"))
      (node (ref "P5") (pin "3") (pinfunction "3_3") (pintype "passive"))
      (node (ref "P6") (pin "2") (pinfunction "2_2") (pintype "passive"))
      (node (ref "P7") (pin "3") (pinfunction "3_3") (pintype "passive"))
      (node (ref "P7") (pin "4") (pinfunction "4_4") (pintype "passive"))
      (node (ref "R1") (pin "2") (pinfunction "2_2") (pintype "passive"))
      (node (ref "R10") (pin "2") (pinfunction "BOT_2") (pintype "passive"))
      (node (ref "R11") (pin "2") (pinfunction "2_2") (pintype "passive"))
      (node (ref "R12") (pin "1") (pinfunction "1_1") (pintype "passive"))
      (node (ref "R13") (pin "1") (pinfunction "1_1") (pintype "passive"))
      (node (ref "R16") (pin "1") (pinfunction "1_1") (pintype "passive"))
      (node (ref "R18") (pin "1") (pinfunction "1_1") (pintype "passive"))
      (node (ref "R2") (pin "2") (pinfunction "2_2") (pintype "passive"))
      (node (ref "R20") (pin "2") (pinfunction "2_2") (pintype "passive"))
      (node (ref "R21") (pin "1") (pinfunction "1_1") (pintype "passive"))
      (node (ref "R23") (pin "1") (pinfunction "1_1") (pintype "passive"))
      (node (ref "R24") (pin "2") (pinfunction "2_2") (pintype "passive"))
      (node (ref "R29") (pin "1") (pinfunction "1_1") (pintype "passive"))
      (node (ref "R3") (pin "2") (pinfunction "2_2") (pintype "passive"))
      (node (ref "R32") (pin "1") (pinfunction "1_1") (pintype "passive"))
      (node (ref "R33") (pin "1") (pinfunction "1_1") (pintype "passive"))
      (node (ref "R34") (pin "1") (pinfunction "1_1") (pintype "passive"))
      (node (ref "R38") (pin "1") (pinfunction "1_1") (pintype "passive"))
      (node (ref "R4") (pin "2") (pinfunction "2_2") (pintype "passive"))
      (node (ref "R40") (pin "1") (pinfunction "1_1") (pintype "passive"))
      (node (ref "R43") (pin "1") (pinfunction "1_1") (pintype "passive"))
      (node (ref "R44") (pin "1") (pinfunction "1_1") (pintype "passive"))
      (node (ref "R9") (pin "2") (pinfunction "BOT_2") (pintype "passive"))
      (node (ref "U1") (pin "5") (pinfunction "5_5") (pintype "passive"))
      (node (ref "U1") (pin "6") (pinfunction "6_6") (pintype "passive"))
      (node (ref "U2") (pin "8") (pinfunction "GND_8") (pintype "passive"))
      (node (ref "U3") (pin "5") (pinfunction "GND_5") (pintype "passive"))
      (node (ref "U4") (pin "1") (pinfunction "S1_1") (pintype "passive"))
      (node (ref "U4") (pin "3") (pinfunction "S2_3") (pintype "passive"))
      (node (ref "U5") (pin "21") (pinfunction "GND_21") (pintype "passive"))
      (node (ref "U5") (pin "3") (pinfunction "GND_3") (pintype "passive"))
      (node (ref "U5") (pin "5") (pinfunction "GND_5") (pintype "power_in"))
      (node (ref "U6") (pin "5") (pinfunction "GND_5") (pintype "passive"))
      (node (ref "U7") (pin "5") (pinfunction "GND_5") (pintype "passive"))
    )
    (net (code "23") (name "Net-(C22-Pad2)") (class "Default")
      (node (ref "C22") (pin "2") (pinfunction "2_2") (pintype "passive"))
      (node (ref "R23") (pin "2") (pinfunction "2_2") (pintype "passive"))
    )
    (net (code "24") (name "Net-(C33-Pad2)") (class "Default")
      (node (ref "C33") (pin "2") (pinfunction "2_2") (pintype "passive"))
      (node (ref "R34") (pin "2") (pinfunction "2_2") (pintype "passive"))
    )
    (net (code "25") (name "Net-(C38-Pad2)") (class "Default")
      (node (ref "C38") (pin "2") (pinfunction "2_2") (pintype "passive"))
      (node (ref "R40") (pin "2") (pinfunction "2_2") (pintype "passive"))
    )
    (net (code "26") (name "Net-(D1-A)") (class "Default")
      (node (ref "D1") (pin "1") (pinfunction "A_1") (pintype "passive"))
      (node (ref "DC1") (pin "2") (pinfunction "2_2") (pintype "passive"))
    )
    (net (code "27") (name "Net-(D1-K)") (class "Default")
      (node (ref "D1") (pin "2") (pinfunction "K_2") (pintype "passive"))
      (node (ref "P1") (pin "1") (pinfunction "1_1") (pintype "passive"))
    )
    (net (code "28") (name "Net-(D2-K)") (class "Default")
      (node (ref "D2") (pin "2") (pinfunction "K_2") (pintype "passive"))
      (node (ref "R11") (pin "1") (pinfunction "1_1") (pintype "passive"))
    )
    (net (code "29") (name "Net-(D3-K)") (class "Default")
      (node (ref "C15") (pin "1") (pinfunction "1_1") (pintype "passive"))
      (node (ref "D3") (pin "2") (pinfunction "K_2") (pintype "passive"))
      (node (ref "L1") (pin "2") (pinfunction "2_2") (pintype "passive"))
      (node (ref "U3") (pin "1") (pinfunction "SW_1") (pintype "passive"))
    )
    (net (code "30") (name "Net-(D4-K)") (class "Default")
      (node (ref "C28") (pin "1") (pinfunction "1_1") (pintype "passive"))
      (node (ref "D4") (pin "2") (pinfunction "K_2") (pintype "passive"))
      (node (ref "L2") (pin "2") (pinfunction "2_2") (pintype "passive"))
      (node (ref "U6") (pin "1") (pinfunction "SW_1") (pintype "passive"))
    )
    (net (code "31") (name "Net-(D5-K)") (class "Default")
      (node (ref "C35") (pin "1") (pinfunction "1_1") (pintype "passive"))
      (node (ref "D5") (pin "2") (pinfunction "K_2") (pintype "passive"))
      (node (ref "L3") (pin "2") (pinfunction "2_2") (pintype "passive"))
      (node (ref "U7") (pin "1") (pinfunction "SW_1") (pintype "passive"))
    )
    (net (code "32") (name "Net-(IC1-CP1)") (class "Default")
      (node (ref "C7") (pin "2") (pinfunction "2_2") (pintype "passive"))
      (node (ref "IC1") (pin "4") (pinfunction "CP1_4") (pintype "passive"))
    )
    (net (code "33") (name "Net-(IC1-CP2)") (class "Default")
      (node (ref "C7") (pin "1") (pinfunction "1_1") (pintype "passive"))
      (node (ref "IC1") (pin "5") (pinfunction "CP2_5") (pintype "passive"))
    )
    (net (code "34") (name "Net-(IC1-OUT1A)") (class "Default")
      (node (ref "IC1") (pin "24") (pinfunction "OUT1A_24") (pintype "passive"))
      (node (ref "JP1") (pin "3") (pinfunction "3_3") (pintype "passive"))
    )
    (net (code "35") (name "Net-(IC1-OUT1B)") (class "Default")
      (node (ref "IC1") (pin "21") (pinfunction "OUT1B_21") (pintype "passive"))
      (node (ref "JP1") (pin "4") (pinfunction "4_4") (pintype "passive"))
    )
    (net (code "36") (name "Net-(IC1-OUT2A)") (class "Default")
      (node (ref "IC1") (pin "26") (pinfunction "OUT2A_26") (pintype "passive"))
      (node (ref "JP1") (pin "2") (pinfunction "2_2") (pintype "passive"))
    )
    (net (code "37") (name "Net-(IC1-OUT2B)") (class "Default")
      (node (ref "IC1") (pin "1") (pinfunction "OUT2B_1") (pintype "passive"))
      (node (ref "JP1") (pin "1") (pinfunction "1_1") (pintype "passive"))
    )
    (net (code "38") (name "Net-(IC1-REF)") (class "Default")
      (node (ref "IC1") (pin "17") (pinfunction "REF_17") (pintype "passive"))
      (node (ref "R9") (pin "3") (pinfunction "TAP_3") (pintype "passive"))
    )
    (net (code "39") (name "Net-(IC1-RESET)") (class "Default")
      (node (ref "IC1") (pin "12") (pinfunction "RESET_12") (pintype "passive"))
      (node (ref "IC1") (pin "14") (pinfunction "SLEEP_14") (pintype "passive"))
      (node (ref "R14") (pin "1") (pinfunction "1_1") (pintype "passive"))
    )
    (net (code "40") (name "Net-(IC1-ROSC)") (class "Default")
      (node (ref "IC1") (pin "13") (pinfunction "ROSC_13") (pintype "passive"))
      (node (ref "R12") (pin "2") (pinfunction "2_2") (pintype "passive"))
    )
    (net (code "41") (name "Net-(IC1-SENSE1)") (class "Default")
      (node (ref "IC1") (pin "23") (pinfunction "SENSE1_23") (pintype "passive"))
      (node (ref "R2") (pin "1") (pinfunction "1_1") (pintype "passive"))
    )
    (net (code "42") (name "Net-(IC1-SENSE2)") (class "Default")
      (node (ref "IC1") (pin "27") (pinfunction "SENSE2_27") (pintype "passive"))
      (node (ref "R1") (pin "1") (pinfunction "1_1") (pintype "passive"))
    )
    (net (code "43") (name "Net-(IC1-VCP)") (class "Default")
      (node (ref "C11") (pin "2") (pinfunction "2_2") (pintype "passive"))
      (node (ref "IC1") (pin "6") (pinfunction "VCP_6") (pintype "passive"))
    )
    (net (code "44") (name "Net-(IC1-VREG)") (class "Default")
      (node (ref "C13") (pin "2") (pinfunction "2_2") (pintype "passive"))
      (node (ref "IC1") (pin "8") (pinfunction "VREG_8") (pintype "passive"))
    )
    (net (code "45") (name "Net-(IC2-CP1)") (class "Default")
      (node (ref "C9") (pin "2") (pinfunction "2_2") (pintype "passive"))
      (node (ref "IC2") (pin "4") (pinfunction "CP1_4") (pintype "passive"))
    )
    (net (code "46") (name "Net-(IC2-CP2)") (class "Default")
      (node (ref "C9") (pin "1") (pinfunction "1_1") (pintype "passive"))
      (node (ref "IC2") (pin "5") (pinfunction "CP2_5") (pintype "passive"))
    )
    (net (code "47") (name "Net-(IC2-OUT1A)") (class "Default")
      (node (ref "IC2") (pin "24") (pinfunction "OUT1A_24") (pintype "passive"))
      (node (ref "JP2") (pin "3") (pinfunction "3_3") (pintype "passive"))
    )
    (net (code "48") (name "Net-(IC2-OUT1B)") (class "Default")
      (node (ref "IC2") (pin "21") (pinfunction "OUT1B_21") (pintype "passive"))
      (node (ref "JP2") (pin "4") (pinfunction "4_4") (pintype "passive"))
    )
    (net (code "49") (name "Net-(IC2-OUT2A)") (class "Default")
      (node (ref "IC2") (pin "26") (pinfunction "OUT2A_26") (pintype "passive"))
      (node (ref "JP2") (pin "2") (pinfunction "2_2") (pintype "passive"))
    )
    (net (code "50") (name "Net-(IC2-OUT2B)") (class "Default")
      (node (ref "IC2") (pin "1") (pinfunction "OUT2B_1") (pintype "passive"))
      (node (ref "JP2") (pin "1") (pinfunction "1_1") (pintype "passive"))
    )
    (net (code "51") (name "Net-(IC2-REF)") (class "Default")
      (node (ref "IC2") (pin "17") (pinfunction "REF_17") (pintype "passive"))
      (node (ref "R10") (pin "3") (pinfunction "TAP_3") (pintype "passive"))
    )
    (net (code "52") (name "Net-(IC2-RESET)") (class "Default")
      (node (ref "IC2") (pin "12") (pinfunction "RESET_12") (pintype "passive"))
      (node (ref "IC2") (pin "14") (pinfunction "SLEEP_14") (pintype "passive"))
      (node (ref "R15") (pin "1") (pinfunction "1_1") (pintype "passive"))
    )
    (net (code "53") (name "Net-(IC2-ROSC)") (class "Default")
      (node (ref "IC2") (pin "13") (pinfunction "ROSC_13") (pintype "passive"))
      (node (ref "R13") (pin "2") (pinfunction "2_2") (pintype "passive"))
    )
    (net (code "54") (name "Net-(IC2-SENSE1)") (class "Default")
      (node (ref "IC2") (pin "23") (pinfunction "SENSE1_23") (pintype "passive"))
      (node (ref "R4") (pin "1") (pinfunction "1_1") (pintype "passive"))
    )
    (net (code "55") (name "Net-(IC2-SENSE2)") (class "Default")
      (node (ref "IC2") (pin "27") (pinfunction "SENSE2_27") (pintype "passive"))
      (node (ref "R3") (pin "1") (pinfunction "1_1") (pintype "passive"))
    )
    (net (code "56") (name "Net-(IC2-VCP)") (class "Default")
      (node (ref "C12") (pin "2") (pinfunction "2_2") (pintype "passive"))
      (node (ref "IC2") (pin "6") (pinfunction "VCP_6") (pintype "passive"))
    )
    (net (code "57") (name "Net-(IC2-VREG)") (class "Default")
      (node (ref "C14") (pin "2") (pinfunction "2_2") (pintype "passive"))
      (node (ref "IC2") (pin "8") (pinfunction "VREG_8") (pintype "passive"))
    )
    (net (code "58") (name "Net-(R9-TOP)") (class "Default")
      (node (ref "R5") (pin "1") (pinfunction "1_1") (pintype "passive"))
      (node (ref "R9") (pin "1") (pinfunction "TOP_1") (pintype "passive"))
    )
    (net (code "59") (name "Net-(R10-TOP)") (class "Default")
      (node (ref "R10") (pin "1") (pinfunction "TOP_1") (pintype "passive"))
      (node (ref "R6") (pin "1") (pinfunction "1_1") (pintype "passive"))
    )
    (net (code "60") (name "Net-(R22-Pad2)") (class "Default")
      (node (ref "R22") (pin "2") (pinfunction "2_2") (pintype "passive"))
      (node (ref "U4") (pin "5") (pinfunction "D2_5") (pintype "passive"))
      (node (ref "U4") (pin "6") (pinfunction "D2_6") (pintype "passive"))
    )
    (net (code "61") (name "Net-(R26-TAP)") (class "Default")
      (node (ref "R21") (pin "2") (pinfunction "2_2") (pintype "passive"))
      (node (ref "R26") (pin "3") (pinfunction "TAP_3") (pintype "passive"))
      (node (ref "U3") (pin "4") (pinfunction "FB_4") (pintype "passive"))
    )
    (net (code "62") (name "Net-(R35-Pad1)") (class "Default")
      (node (ref "R35") (pin "1") (pinfunction "1_1") (pintype "passive"))
      (node (ref "R37") (pin "2") (pinfunction "2_2") (pintype "passive"))
    )
    (net (code "63") (name "Net-(R41-Pad1)") (class "Default")
      (node (ref "R41") (pin "1") (pinfunction "1_1") (pintype "passive"))
      (node (ref "R42") (pin "2") (pinfunction "2_2") (pintype "passive"))
    )
    (net (code "64") (name "Net-(U2-DTR)") (class "Default")
      (node (ref "C18") (pin "1") (pinfunction "1_1") (pintype "passive"))
      (node (ref "U2") (pin "15") (pinfunction "DTR_15") (pintype "passive"))
    )
    (net (code "65") (name "Net-(U2-RXD)") (class "Default")
      (node (ref "R19") (pin "2") (pinfunction "2_2") (pintype "passive"))
      (node (ref "U2") (pin "4") (pinfunction "RXD_4") (pintype "passive"))
    )
    (net (code "66") (name "Net-(U2-TXD)") (class "Default")
      (node (ref "R25") (pin "1") (pinfunction "1_1") (pintype "passive"))
      (node (ref "U2") (pin "3") (pinfunction "TXD_3") (pintype "passive"))
    )
    (net (code "67") (name "Net-(U2-V3)") (class "Default")
      (node (ref "C17") (pin "2") (pinfunction "2_2") (pintype "passive"))
      (node (ref "U2") (pin "5") (pinfunction "V3_5") (pintype "passive"))
    )
    (net (code "68") (name "Net-(U2-XI)") (class "Default")
      (node (ref "C21") (pin "2") (pinfunction "2_2") (pintype "passive"))
      (node (ref "U2") (pin "9") (pinfunction "XI_9") (pintype "passive"))
      (node (ref "Y1") (pin "1") (pinfunction "OSC1_1") (pintype "passive"))
    )
    (net (code "69") (name "Net-(U2-XO)") (class "Default")
      (node (ref "C23") (pin "2") (pinfunction "2_2") (pintype "passive"))
      (node (ref "U2") (pin "10") (pinfunction "XO_10") (pintype "passive"))
      (node (ref "Y1") (pin "2") (pinfunction "OSC2_2") (pintype "passive"))
    )
    (net (code "70") (name "Net-(U3-BSP)") (class "Default")
      (node (ref "C15") (pin "2") (pinfunction "2_2") (pintype "passive"))
      (node (ref "U3") (pin "8") (pinfunction "BSP_8") (pintype "passive"))
    )
    (net (code "71") (name "Net-(U3-COMP)") (class "Default")
      (node (ref "C22") (pin "1") (pinfunction "1_1") (pintype "passive"))
      (node (ref "U3") (pin "3") (pinfunction "COMP_3") (pintype "passive"))
    )
    (net (code "72") (name "Net-(U3-EN)") (class "Default")
      (node (ref "R16") (pin "2") (pinfunction "2_2") (pintype "passive"))
      (node (ref "R17") (pin "2") (pinfunction "2_2") (pintype "passive"))
      (node (ref "U3") (pin "2") (pinfunction "EN_2") (pintype "passive"))
    )
    (net (code "73") (name "Net-(U3-FREQ)") (class "Default")
      (node (ref "R18") (pin "2") (pinfunction "2_2") (pintype "passive"))
      (node (ref "U3") (pin "6") (pinfunction "FREQ_6") (pintype "passive"))
    )
    (net (code "74") (name "Net-(U5-PB6_(XTAL1{slash}TOSC1))") (class "Default")
      (node (ref "C29") (pin "1") (pinfunction "1_1") (pintype "passive"))
      (node (ref "Q1") (pin "2") (pinfunction "2_2") (pintype "passive"))
      (node (ref "R30") (pin "1") (pinfunction "1_1") (pintype "passive"))
      (node (ref "U5") (pin "7") (pinfunction "PB6_(XTAL1/TOSC1)_7") (pintype "passive"))
    )
    (net (code "75") (name "Net-(U5-PB7_(XTAL2{slash}TOSC2))") (class "Default")
      (node (ref "C31") (pin "1") (pinfunction "1_1") (pintype "passive"))
      (node (ref "Q1") (pin "1") (pinfunction "1_1") (pintype "passive"))
      (node (ref "R30") (pin "2") (pinfunction "2_2") (pintype "passive"))
      (node (ref "U5") (pin "8") (pinfunction "PB7_(XTAL2/TOSC2)_8") (pintype "passive"))
    )
    (net (code "76") (name "Net-(U6-BSP)") (class "Default")
      (node (ref "C28") (pin "2") (pinfunction "2_2") (pintype "passive"))
      (node (ref "U6") (pin "8") (pinfunction "BSP_8") (pintype "passive"))
    )
    (net (code "77") (name "Net-(U6-COMP)") (class "Default")
      (node (ref "C33") (pin "1") (pinfunction "1_1") (pintype "passive"))
      (node (ref "U6") (pin "3") (pinfunction "COMP_3") (pintype "passive"))
    )
    (net (code "78") (name "Net-(U6-EN)") (class "Default")
      (node (ref "R29") (pin "2") (pinfunction "2_2") (pintype "passive"))
      (node (ref "R31") (pin "2") (pinfunction "2_2") (pintype "passive"))
      (node (ref "U6") (pin "2") (pinfunction "EN_2") (pintype "passive"))
    )
    (net (code "79") (name "Net-(U6-FB)") (class "Default")
      (node (ref "R33") (pin "2") (pinfunction "2_2") (pintype "passive"))
      (node (ref "R35") (pin "2") (pinfunction "2_2") (pintype "passive"))
      (node (ref "U6") (pin "4") (pinfunction "FB_4") (pintype "passive"))
    )
    (net (code "80") (name "Net-(U6-FREQ)") (class "Default")
      (node (ref "R32") (pin "2") (pinfunction "2_2") (pintype "passive"))
      (node (ref "U6") (pin "6") (pinfunction "FREQ_6") (pintype "passive"))
    )
    (net (code "81") (name "Net-(U7-BSP)") (class "Default")
      (node (ref "C35") (pin "2") (pinfunction "2_2") (pintype "passive"))
      (node (ref "U7") (pin "8") (pinfunction "BSP_8") (pintype "passive"))
    )
    (net (code "82") (name "Net-(U7-COMP)") (class "Default")
      (node (ref "C38") (pin "1") (pinfunction "1_1") (pintype "passive"))
      (node (ref "U7") (pin "3") (pinfunction "COMP_3") (pintype "passive"))
    )
    (net (code "83") (name "Net-(U7-EN)") (class "Default")
      (node (ref "R38") (pin "2") (pinfunction "2_2") (pintype "passive"))
      (node (ref "R39") (pin "2") (pinfunction "2_2") (pintype "passive"))
      (node (ref "U7") (pin "2") (pinfunction "EN_2") (pintype "passive"))
    )
    (net (code "84") (name "Net-(U7-FB)") (class "Default")
      (node (ref "R41") (pin "2") (pinfunction "2_2") (pintype "passive"))
      (node (ref "R43") (pin "2") (pinfunction "2_2") (pintype "passive"))
      (node (ref "U7") (pin "4") (pinfunction "FB_4") (pintype "passive"))
    )
    (net (code "85") (name "Net-(U7-FREQ)") (class "Default")
      (node (ref "R44") (pin "2") (pinfunction "2_2") (pintype "passive"))
      (node (ref "U7") (pin "6") (pinfunction "FREQ_6") (pintype "passive"))
    )
    (net (code "86") (name "VCC") (class "Default")
      (node (ref "C10") (pin "1") (pinfunction "1_1") (pintype "passive"))
      (node (ref "C16") (pin "2") (pinfunction "2_2") (pintype "passive"))
      (node (ref "C27") (pin "2") (pinfunction "2_2") (pintype "passive"))
      (node (ref "C30") (pin "2") (pinfunction "2_2") (pintype "passive"))
      (node (ref "C34") (pin "1") (pinfunction "1_1") (pintype "passive"))
      (node (ref "C8") (pin "1") (pinfunction "1_1") (pintype "passive"))
      (node (ref "D2") (pin "1") (pinfunction "A_1") (pintype "passive"))
      (node (ref "IC1") (pin "10") (pinfunction "MS2_10") (pintype "passive"))
      (node (ref "IC1") (pin "15") (pinfunction "VDD_15") (pintype "passive"))
      (node (ref "IC1") (pin "9") (pinfunction "MS1_9") (pintype "passive"))
      (node (ref "IC2") (pin "10") (pinfunction "MS2_10") (pintype "passive"))
      (node (ref "IC2") (pin "15") (pinfunction "VDD_15") (pintype "passive"))
      (node (ref "IC2") (pin "9") (pinfunction "MS1_9") (pintype "passive"))
      (node (ref "ICSP1") (pin "2") (pinfunction "2_2") (pintype "passive"))
      (node (ref "L2") (pin "1") (pinfunction "1_1") (pintype "passive"))
      (node (ref "R14") (pin "2") (pinfunction "2_2") (pintype "passive"))
      (node (ref "R15") (pin "2") (pinfunction "2_2") (pintype "passive"))
      (node (ref "R27") (pin "2") (pinfunction "2_2") (pintype "passive"))
      (node (ref "R28") (pin "2") (pinfunction "2_2") (pintype "passive"))
      (node (ref "R36") (pin "2") (pinfunction "2_2") (pintype "passive"))
      (node (ref "R37") (pin "1") (pinfunction "1_1") (pintype "passive"))
      (node (ref "R5") (pin "2") (pinfunction "2_2") (pintype "passive"))
      (node (ref "R6") (pin "2") (pinfunction "2_2") (pintype "passive"))
      (node (ref "R7") (pin "2") (pinfunction "2_2") (pintype "passive"))
      (node (ref "R8") (pin "2") (pinfunction "2_2") (pintype "passive"))
      (node (ref "U2") (pin "19") (pinfunction "VCC_19") (pintype "passive"))
      (node (ref "U5") (pin "18") (pinfunction "AVCC_18") (pintype "passive"))
      (node (ref "U5") (pin "20") (pinfunction "AREF_20") (pintype "input"))
      (node (ref "U5") (pin "4") (pinfunction "VCC_4") (pintype "power_in"))
      (node (ref "U5") (pin "6") (pinfunction "VCC_6") (pintype "passive"))
    )
    (net (code "87") (name "VCC_LASER") (class "Default")
      (node (ref "C25") (pin "1") (pinfunction "1_1") (pintype "passive"))
      (node (ref "L1") (pin "1") (pinfunction "1_1") (pintype "passive"))
      (node (ref "P3") (pin "1") (pinfunction "1_1") (pintype "passive"))
      (node (ref "R26") (pin "2") (pinfunction "BOT_2") (pintype "passive"))
    )
    (net (code "88") (name "VMOT") (class "Default")
      (node (ref "C1") (pin "1") (pinfunction "1_1") (pintype "passive"))
      (node (ref "C11") (pin "1") (pinfunction "1_1") (pintype "passive"))
      (node (ref "C12") (pin "1") (pinfunction "1_1") (pintype "passive"))
      (node (ref "C2") (pin "1") (pinfunction "1_1") (pintype "passive"))
      (node (ref "C20") (pin "1") (pinfunction "1_1") (pintype "passive"))
      (node (ref "C3") (pin "2") (pinfunction "2_2") (pintype "passive"))
      (node (ref "C32") (pin "1") (pinfunction "1_1") (pintype "passive"))
      (node (ref "C36") (pin "1") (pinfunction "1_1") (pintype "passive"))
      (node (ref "C4") (pin "1") (pinfunction "1_1") (pintype "passive"))
      (node (ref "C5") (pin "2") (pinfunction "2_2") (pintype "passive"))
      (node (ref "C6") (pin "1") (pinfunction "1_1") (pintype "passive"))
      (node (ref "IC1") (pin "22") (pinfunction "VBB1_22") (pintype "passive"))
      (node (ref "IC1") (pin "28") (pinfunction "VBB2_28") (pintype "passive"))
      (node (ref "IC2") (pin "22") (pinfunction "VBB1_22") (pintype "passive"))
      (node (ref "IC2") (pin "28") (pinfunction "VBB2_28") (pintype "passive"))
      (node (ref "P1") (pin "2") (pinfunction "2_2") (pintype "passive"))
      (node (ref "P7") (pin "1") (pinfunction "1_1") (pintype "passive"))
      (node (ref "R17") (pin "1") (pinfunction "1_1") (pintype "passive"))
      (node (ref "R31") (pin "1") (pinfunction "1_1") (pintype "passive"))
      (node (ref "R39") (pin "1") (pinfunction "1_1") (pintype "passive"))
      (node (ref "U3") (pin "7") (pinfunction "VIN_7") (pintype "passive"))
      (node (ref "U6") (pin "7") (pinfunction "VIN_7") (pintype "passive"))
      (node (ref "U7") (pin "7") (pinfunction "VIN_7") (pintype "passive"))
    )
    (net (code "89") (name "V_PRO") (class "Default")
      (node (ref "C37") (pin "1") (pinfunction "1_1") (pintype "passive"))
      (node (ref "L3") (pin "1") (pinfunction "1_1") (pintype "passive"))
      (node (ref "P6") (pin "1") (pinfunction "1_1") (pintype "passive"))
      (node (ref "P7") (pin "2") (pinfunction "2_2") (pintype "passive"))
      (node (ref "R42") (pin "1") (pinfunction "1_1") (pintype "passive"))
    )
    (net (code "90") (name "unconnected-(IC1-MS3-Pad11)") (class "Default")
      (node (ref "IC1") (pin "11") (pinfunction "MS3_11") (pintype "passive"))
    )
    (net (code "91") (name "unconnected-(IC2-MS3-Pad11)") (class "Default")
      (node (ref "IC2") (pin "11") (pinfunction "MS3_11") (pintype "passive"))
    )
    (net (code "92") (name "unconnected-(R26-TOP-Pad1)") (class "Default")
      (node (ref "R26") (pin "1") (pinfunction "TOP_1") (pintype "passive"))
    )
    (net (code "93") (name "unconnected-(U1-Pad1)") (class "Default")
      (node (ref "U1") (pin "1") (pinfunction "1_1") (pintype "passive"))
    )
    (net (code "94") (name "unconnected-(U1-Pad4)") (class "Default")
      (node (ref "U1") (pin "4") (pinfunction "4_4") (pintype "passive"))
    )
    (net (code "95") (name "unconnected-(U2-NOS#-Pad20)") (class "Default")
      (node (ref "U2") (pin "20") (pinfunction "NOS#_20") (pintype "passive"))
    )
    (net (code "96") (name "unconnected-(U5-(ADC1)_PC1-Pad24)") (class "Default")
      (node (ref "U5") (pin "24") (pinfunction "(ADC1)_PC1_24") (pintype "bidirectional"))
    )
    (net (code "97") (name "unconnected-(U5-(ADC2)_PC2-Pad25)") (class "Default")
      (node (ref "U5") (pin "25") (pinfunction "(ADC2)_PC2_25") (pintype "bidirectional"))
    )
    (net (code "98") (name "unconnected-(U5-(ADC3)_PC3-Pad26)") (class "Default")
      (node (ref "U5") (pin "26") (pinfunction "(ADC3)_PC3_26") (pintype "bidirectional"))
    )
    (net (code "99") (name "unconnected-(U5-(ADC4{slash}SDA)_PC4-Pad27)") (class "Default")
      (node (ref "U5") (pin "27") (pinfunction "(ADC4/SDA)_PC4_27") (pintype "bidirectional"))
    )
    (net (code "100") (name "unconnected-(U5-(ADC5{slash}SCL)_PC5-Pad28)") (class "Default")
      (node (ref "U5") (pin "28") (pinfunction "(ADC5/SCL)_PC5_28") (pintype "bidirectional"))
    )
  )
)
